# MCU_Debug.net
KiCad netlist of a schematic drawn in Altium Designer
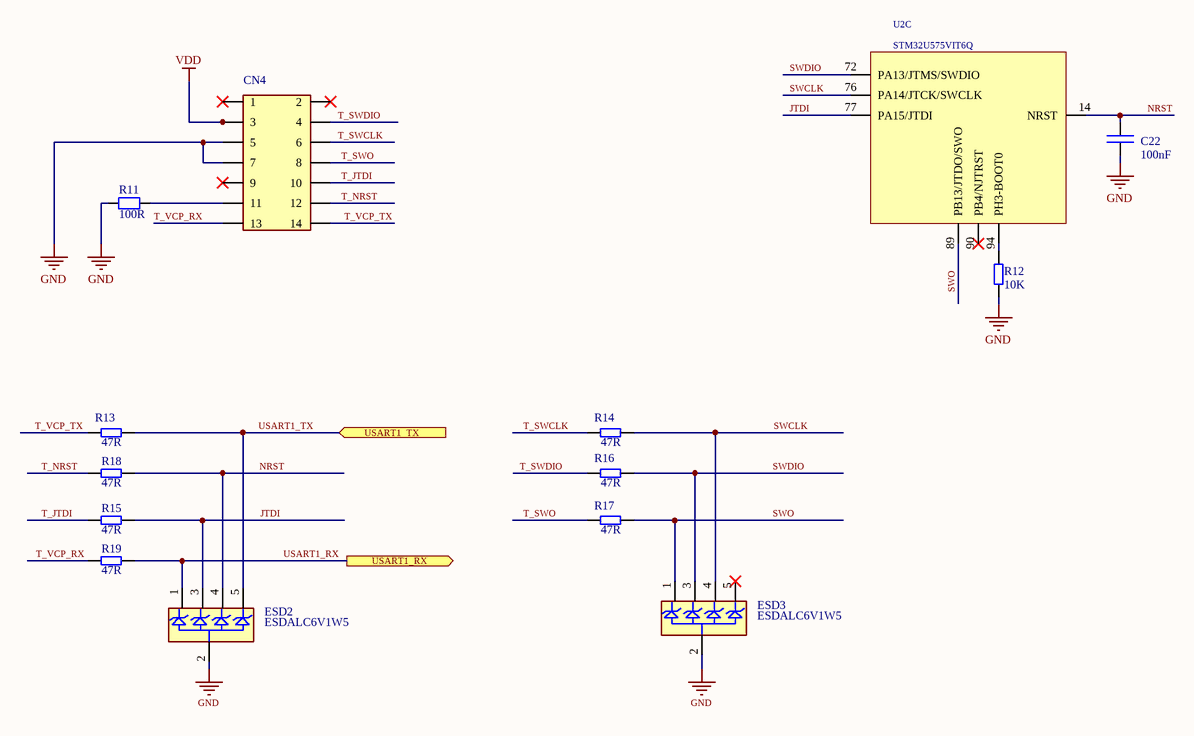
[diagram p0: MCU_Debug.SchDoc]

(export (version "E")
  (design (tool "Eeschema 10.0.6"))
  (components
    (comp (ref "C22")
      (value "100nF")
      (footprint "CAP_SM0603_YAGEOCC2_N")
      (description "CAP 100nF SM0603 X7R 50V YAGEO CC2")
      (fields
        (field (name "MANUFACTURER") "Yageo")
        (field (name "MANUFACTURER PART NUMBER") "CC0603KRX7R9BB104")
      )
      (libsource (lib "yageo") (part "CC0603KRX7R9BB104"))
    )
    (comp (ref "CN4")
      (value "20021511-00014T4LF")
      (footprint "2002151100014T4LF")
      (description "1.27mm (0.05in.) pitch, Shrouded pin header, 14 contacts")
      (fields (field (name "MANUFACTURER") "Amphenol ICC"))
      (libsource (lib "flowmeet") (part "20021511-00014T4LF"))
    )
    (comp (ref "ESD2")
      (value "ESDALC6V1W5")
      (footprint "ESDALC6V1W5")
      (fields (field (name "MANUFACTURER") "ST"))
      (libsource (lib "flowmeet") (part "ESDALC6V1W5"))
    )
    (comp (ref "ESD3")
      (value "ESDALC6V1W5")
      (footprint "ESDALC6V1W5")
      (fields (field (name "MANUFACTURER") "ST"))
      (libsource (lib "flowmeet") (part "ESDALC6V1W5"))
    )
    (comp (ref "R11")
      (value "100R")
      (footprint "RES_SM0603_YAGEORC_N")
      (description "RES 100R SM0603 YAGEO RC_L")
      (fields
        (field (name "MANUFACTURER") "Yageo")
        (field (name "MANUFACTURER PART NUMBER") "RC0603FR-07100RL")
      )
      (libsource (lib "yageo") (part "RC0603FR-07100RL"))
    )
    (comp (ref "R12")
      (value "10K")
      (footprint "RES_SM0603_YAGEORC_N")
      (description "RES 10K SM0603 YAGEO RC_L")
      (fields
        (field (name "MANUFACTURER") "Yageo")
        (field (name "MANUFACTURER PART NUMBER") "RC0603FR-0710KL")
      )
      (libsource (lib "yageo") (part "RC0603FR-0710KL"))
    )
    (comp (ref "R13")
      (value "47R")
      (footprint "RES_SM0603_YAGEORC_N")
      (description "RES 47R SM0603 YAGEO RC_L")
      (fields
        (field (name "MANUFACTURER") "Yageo")
        (field (name "MANUFACTURER PART NUMBER") "RC0603FR-0747RL")
      )
      (libsource (lib "yageo") (part "RC0603FR-0747RL"))
    )
    (comp (ref "R14")
      (value "47R")
      (footprint "RES_SM0603_YAGEORC_N")
      (description "RES 47R SM0603 YAGEO RC_L")
      (fields
        (field (name "MANUFACTURER") "Yageo")
        (field (name "MANUFACTURER PART NUMBER") "RC0603FR-0747RL")
      )
      (libsource (lib "yageo") (part "RC0603FR-0747RL"))
    )
    (comp (ref "R15")
      (value "47R")
      (footprint "RES_SM0603_YAGEORC_N")
      (description "RES 47R SM0603 YAGEO RC_L")
      (fields
        (field (name "MANUFACTURER") "Yageo")
        (field (name "MANUFACTURER PART NUMBER") "RC0603FR-0747RL")
      )
      (libsource (lib "yageo") (part "RC0603FR-0747RL"))
    )
    (comp (ref "R16")
      (value "47R")
      (footprint "RES_SM0603_YAGEORC_N")
      (description "RES 47R SM0603 YAGEO RC_L")
      (fields
        (field (name "MANUFACTURER") "Yageo")
        (field (name "MANUFACTURER PART NUMBER") "RC0603FR-0747RL")
      )
      (libsource (lib "yageo") (part "RC0603FR-0747RL"))
    )
    (comp (ref "R17")
      (value "47R")
      (footprint "RES_SM0603_YAGEORC_N")
      (description "RES 47R SM0603 YAGEO RC_L")
      (fields
        (field (name "MANUFACTURER") "Yageo")
        (field (name "MANUFACTURER PART NUMBER") "RC0603FR-0747RL")
      )
      (libsource (lib "yageo") (part "RC0603FR-0747RL"))
    )
    (comp (ref "R18")
      (value "47R")
      (footprint "RES_SM0603_YAGEORC_N")
      (description "RES 47R SM0603 YAGEO RC_L")
      (fields
        (field (name "MANUFACTURER") "Yageo")
        (field (name "MANUFACTURER PART NUMBER") "RC0603FR-0747RL")
      )
      (libsource (lib "yageo") (part "RC0603FR-0747RL"))
    )
    (comp (ref "R19")
      (value "47R")
      (footprint "RES_SM0603_YAGEORC_N")
      (description "RES 47R SM0603 YAGEO RC_L")
      (fields
        (field (name "MANUFACTURER") "Yageo")
        (field (name "MANUFACTURER PART NUMBER") "RC0603FR-0747RL")
      )
      (libsource (lib "yageo") (part "RC0603FR-0747RL"))
    )
    (comp (ref "U2")
      (value "STM32U575VIT6Q")
      (footprint "STM32U575VI")
      (fields (field (name "MANUFACTURER") "ST"))
      (libsource (lib "flowmeet") (part "STM32U575VIT6Q"))
    )
  )
  (nets
    (net (code "1") (name "/JTDI") (class "Default")
      (node (ref "ESD2") (pin "3") (pinfunction "I/02_3") (pintype "passive"))
      (node (ref "R15") (pin "2") (pintype "passive"))
      (node (ref "U2") (pin "77") (pinfunction "PA15/JTDI_77") (pintype "passive"))
    )
    (net (code "2") (name "/NRST") (class "Default")
      (node (ref "C22") (pin "1") (pintype "passive"))
      (node (ref "ESD2") (pin "4") (pinfunction "I/03_4") (pintype "passive"))
      (node (ref "R18") (pin "2") (pintype "passive"))
      (node (ref "U2") (pin "14") (pinfunction "NRST_14") (pintype "passive"))
    )
    (net (code "3") (name "/SWCLK") (class "Default")
      (node (ref "ESD3") (pin "4") (pinfunction "I/03_4") (pintype "passive"))
      (node (ref "R14") (pin "2") (pintype "passive"))
      (node (ref "U2") (pin "76") (pinfunction "PA14/JTCK/SWCLK_76") (pintype "passive"))
    )
    (net (code "4") (name "/SWDIO") (class "Default")
      (node (ref "ESD3") (pin "3") (pinfunction "I/02_3") (pintype "passive"))
      (node (ref "R16") (pin "2") (pintype "passive"))
      (node (ref "U2") (pin "72") (pinfunction "PA13/JTMS/SWDIO_72") (pintype "passive"))
    )
    (net (code "5") (name "/SWO") (class "Default")
      (node (ref "ESD3") (pin "1") (pinfunction "I/01_1") (pintype "passive"))
      (node (ref "R17") (pin "2") (pintype "passive"))
      (node (ref "U2") (pin "89") (pinfunction "PB13/JTDO/SWO_89") (pintype "passive"))
    )
    (net (code "6") (name "/T_JTDI") (class "Default")
      (node (ref "CN4") (pin "10") (pinfunction "10_10") (pintype "passive"))
      (node (ref "R15") (pin "1") (pintype "passive"))
    )
    (net (code "7") (name "/T_NRST") (class "Default")
      (node (ref "CN4") (pin "12") (pinfunction "12_12") (pintype "passive"))
      (node (ref "R18") (pin "1") (pintype "passive"))
    )
    (net (code "8") (name "/T_SWCLK") (class "Default")
      (node (ref "CN4") (pin "6") (pinfunction "6_6") (pintype "passive"))
      (node (ref "R14") (pin "1") (pintype "passive"))
    )
    (net (code "9") (name "/T_SWDIO") (class "Default")
      (node (ref "CN4") (pin "4") (pinfunction "4_4") (pintype "passive"))
      (node (ref "R16") (pin "1") (pintype "passive"))
    )
    (net (code "10") (name "/T_SWO") (class "Default")
      (node (ref "CN4") (pin "8") (pinfunction "8_8") (pintype "passive"))
      (node (ref "R17") (pin "1") (pintype "passive"))
    )
    (net (code "11") (name "/T_VCP_RX") (class "Default")
      (node (ref "CN4") (pin "13") (pinfunction "13_13") (pintype "passive"))
      (node (ref "R19") (pin "1") (pintype "passive"))
    )
    (net (code "12") (name "/T_VCP_TX") (class "Default")
      (node (ref "CN4") (pin "14") (pinfunction "14_14") (pintype "passive"))
      (node (ref "R13") (pin "1") (pintype "passive"))
    )
    (net (code "13") (name "/USART1_RX") (class "Default")
      (node (ref "ESD2") (pin "1") (pinfunction "I/01_1") (pintype "passive"))
      (node (ref "R19") (pin "2") (pintype "passive"))
    )
    (net (code "14") (name "/USART1_TX") (class "Default")
      (node (ref "ESD2") (pin "5") (pinfunction "I/04_5") (pintype "passive"))
      (node (ref "R13") (pin "2") (pintype "passive"))
    )
    (net (code "15") (name "GND") (class "Default")
      (node (ref "C22") (pin "2") (pintype "passive"))
      (node (ref "CN4") (pin "5") (pinfunction "5_5") (pintype "passive"))
      (node (ref "CN4") (pin "7") (pinfunction "7_7") (pintype "passive"))
      (node (ref "ESD2") (pin "2") (pinfunction "GND_2") (pintype "passive"))
      (node (ref "ESD3") (pin "2") (pinfunction "GND_2") (pintype "passive"))
      (node (ref "R11") (pin "1") (pintype "passive"))
      (node (ref "R12") (pin "1") (pintype "passive"))
    )
    (net (code "16") (name "Net-(CN4-Pad11)") (class "Default")
      (node (ref "CN4") (pin "11") (pinfunction "11_11") (pintype "passive"))
      (node (ref "R11") (pin "2") (pintype "passive"))
    )
    (net (code "17") (name "Net-(U2C-PH3-BOOT0)") (class "Default")
      (node (ref "R12") (pin "2") (pintype "passive"))
      (node (ref "U2") (pin "94") (pinfunction "PH3-BOOT0_94") (pintype "passive"))
    )
    (net (code "18") (name "VDD") (class "Default")
      (node (ref "CN4") (pin "3") (pinfunction "3_3") (pintype "passive"))
    )
    (net (code "19") (name "unconnected-(CN4-Pad1)") (class "Default")
      (node (ref "CN4") (pin "1") (pinfunction "1_1") (pintype "passive+no_connect"))
    )
    (net (code "20") (name "unconnected-(CN4-Pad2)") (class "Default")
      (node (ref "CN4") (pin "2") (pinfunction "2_2") (pintype "passive+no_connect"))
    )
    (net (code "21") (name "unconnected-(CN4-Pad9)") (class "Default")
      (node (ref "CN4") (pin "9") (pinfunction "9_9") (pintype "passive+no_connect"))
    )
    (net (code "22") (name "unconnected-(ESD3-I{slash}04-Pad5)") (class "Default")
      (node (ref "ESD3") (pin "5") (pinfunction "I/04_5") (pintype "passive+no_connect"))
    )
    (net (code "23") (name "unconnected-(U2C-PB4{slash}NJTRST-Pad90)") (class "Default")
      (node (ref "U2") (pin "90") (pinfunction "PB4/NJTRST_90") (pintype "passive+no_connect"))
    )
  )
)
